# cSLIM-SA_connectors.net
KiCad netlist of a schematic drawn in Altium Designer
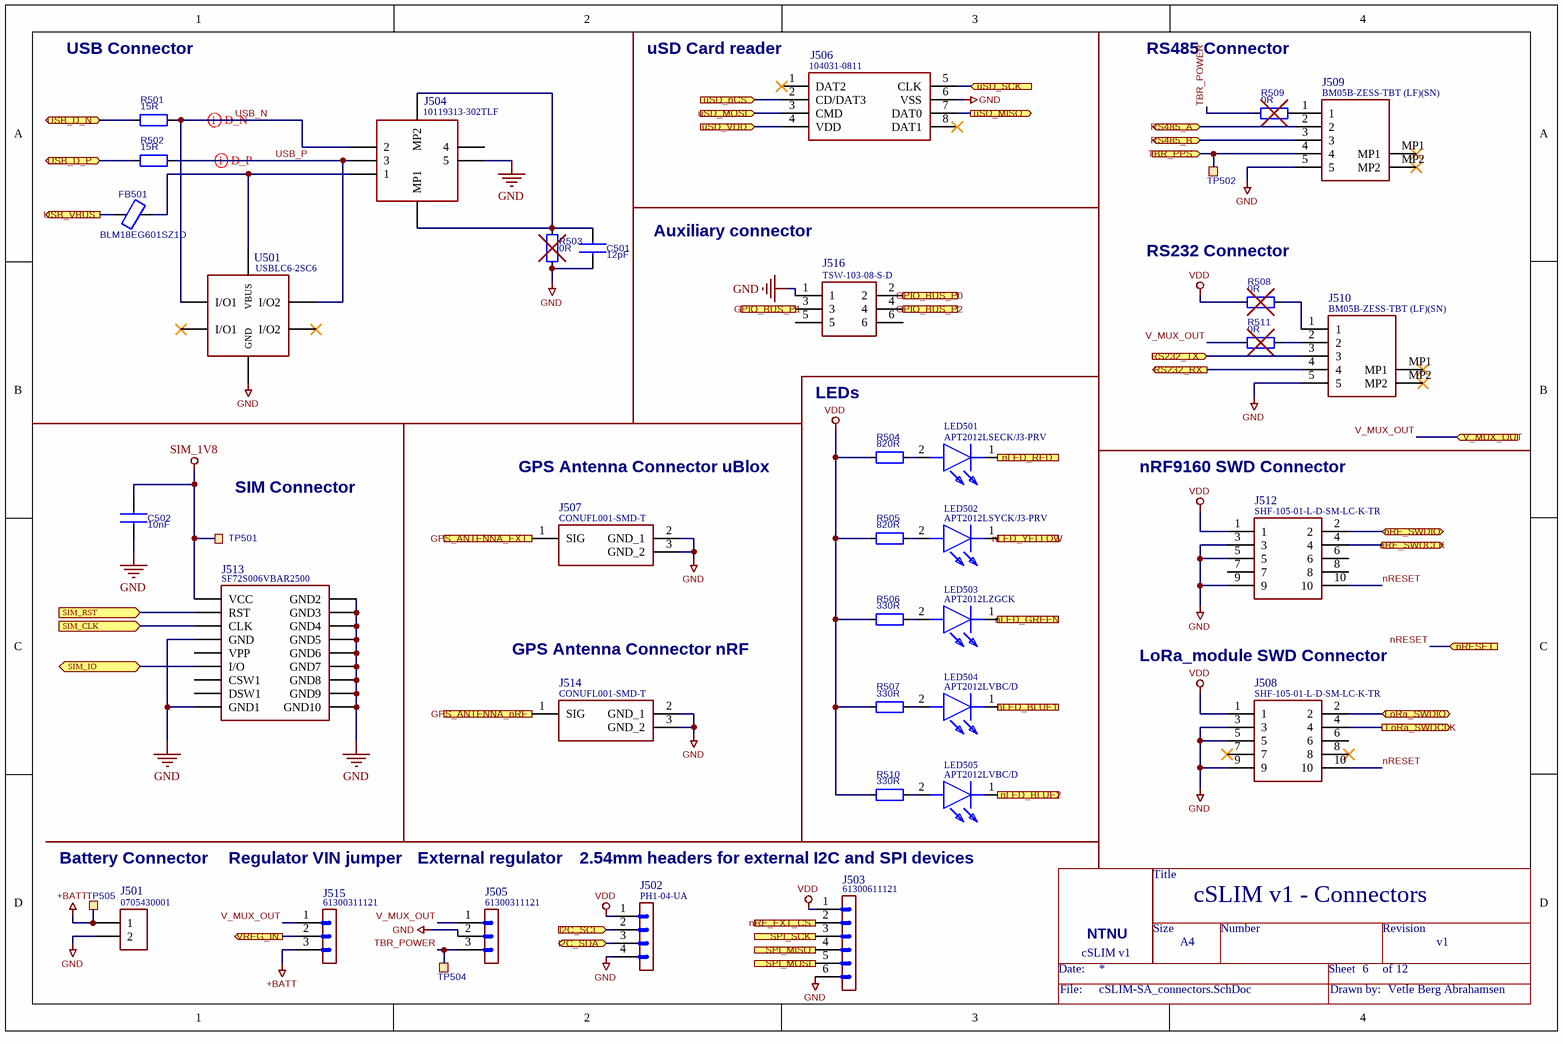
[diagram p0: cSLIM-SA_connectors.SchDoc]

(export (version "E")
  (design (tool "Eeschema 10.0.6"))
  (components
    (comp (ref "C501")
      (value "12pF")
      (footprint "cSLIM-SA:CAPC1608X90N")
      (description "Capacitor")
      (fields (field (name "MANUFACTURER_PART_NUMBER") "0603N120J500CT"))
      (libsource (lib "cSLIM-SA") (part "C"))
    )
    (comp (ref "C502")
      (value "10nF")
      (footprint "cSLIM-SA:CAPC1608X90N")
      (description "Capacitor")
      (fields (field (name "MANUFACTURER_PART_NUMBER") "CL10B103KB8NNNC"))
      (libsource (lib "cSLIM-SA") (part "C"))
    )
    (comp (ref "FB501")
      (value "BLM18EG601SZ1D")
      (footprint "CAPC1608X90N")
      (description "Ferrite bead")
      (libsource (lib "cSLIM-SA") (part "Ferrite_Bead"))
    )
    (comp (ref "J501")
      (value "0705430001")
      (footprint "cSLIM-SA:SHDR2W64P0X254_1X2_737X660X1181P")
      (description "BAT CONN HEADER VERT 2POS 2.54MM")
      (fields
        (field (name "MANUFACTURER_PART_NUMBER") "70543-0001")
        (field (name "MOUSER PART NUMBER") "538-70543-0001")
      )
      (libsource (lib "cSLIM-SA") (part "70543-0001"))
    )
    (comp (ref "J502")
      (value "PH1-04-UA")
      (footprint "cSLIM-SA:HDRV4W64P0X254_1X4_1016X250X901P")
      (description "CONN HEADER VERT 4POS 2.54MM")
      (libsource (lib "cSLIM-SA") (part "PH1-04-UA"))
    )
    (comp (ref "J503")
      (value "61300611121")
      (footprint "cSLIM-SA:HDRV6W64P0X254_1X6_1524X254X869P")
      (description "CONN HEADER VERT 6POS 2.54MM")
      (fields (field (name "MOUSER PART NUMBER") "710-61300611121"))
      (libsource (lib "cSLIM-SA") (part "61300611121"))
    )
    (comp (ref "J504")
      (value "10119313-302TLF")
      (footprint "cSLIM-SA:10119313302TLF")
      (description "USB - mini B USB 2.0 Receptacle Connector 5 Position Through Hole")
      (fields (field (name "MOUSER PART NUMBER") "649-10119313-302TLF"))
      (libsource (lib "cSLIM-SA") (part "10119313-302TLF"))
    )
    (comp (ref "J505")
      (value "61300311121")
      (footprint "cSLIM-SA:HDRV3W64P0X254_1X3_762X254X869P")
      (description "CONN HEADER VERT 3POS 2.54MM")
      (fields (field (name "MOUSER PART NUMBER") "710-61300311121"))
      (libsource (lib "cSLIM-SA") (part "61300311121"))
    )
    (comp (ref "J506")
      (value "104031-0811")
      (footprint "cSLIM-SA:1040310811")
      (description "CONN MICRO SD CARD PUSH-PULL R/A")
      (fields (field (name "MOUSER PART NUMBER") "538-104031-0811"))
      (libsource (lib "cSLIM-SA") (part "104031-0811"))
    )
    (comp (ref "J507")
      (value "CONUFL001-SMD-T")
      (footprint "cSLIM-SA:CONUFL001-SMD")
      (description "CONN UMC JACK STR SMD")
      (fields (field (name "MOUSER PART NUMBER") "712-CONUFL001-SMD-T"))
      (libsource (lib "cSLIM-SA") (part "CONUFL001-SMD-T"))
    )
    (comp (ref "J508")
      (value "SHF-105-01-L-D-SM-LC-K-TR")
      (footprint "cSLIM-SA:SHF10501LDSMLCKTR")
      (description "CONN HEADER SMD 10POS 1.27MM")
      (libsource (lib "cSLIM-SA") (part "SHF-105-01-L-D-SM-LC-K-TR"))
    )
    (comp (ref "J509")
      (value "BM05B-ZESS-TBT (LF)(SN)")
      (footprint "cSLIM-SA:BM05BZESSTBTLFSN")
      (description "RS232/RS485  CONN HEADER SMD 5POS 1.5MM")
      (libsource (lib "cSLIM-SA") (part "BM05B-ZESS-TBT__LF__SN_"))
    )
    (comp (ref "J510")
      (value "BM05B-ZESS-TBT (LF)(SN)")
      (footprint "cSLIM-SA:BM05BZESSTBTLFSN")
      (description "RS232/RS485  CONN HEADER SMD 5POS 1.5MM")
      (libsource (lib "cSLIM-SA") (part "BM05B-ZESS-TBT__LF__SN_"))
    )
    (comp (ref "J512")
      (value "SHF-105-01-L-D-SM-LC-K-TR")
      (footprint "cSLIM-SA:SHF10501LDSMLCKTR")
      (description "CONN HEADER SMD 10POS 1.27MM")
      (libsource (lib "cSLIM-SA") (part "SHF-105-01-L-D-SM-LC-K-TR"))
    )
    (comp (ref "J513")
      (value "SF72S006VBAR2500")
      (footprint "cSLIM-SA:SF72S006VBAR2500")
      (description "NANO SIM CARD PUSH-PUSH")
      (fields (field (name "MOUSER PART NUMBER") "656-SF72S006VBAR2500"))
      (libsource (lib "cSLIM-SA") (part "SF72S006VBAR2500"))
    )
    (comp (ref "J514")
      (value "CONUFL001-SMD-T")
      (footprint "cSLIM-SA:CONUFL001-SMD")
      (description "CONN UMC JACK STR SMD")
      (fields (field (name "MOUSER PART NUMBER") "712-CONUFL001-SMD-T"))
      (libsource (lib "cSLIM-SA") (part "CONUFL001-SMD-T"))
    )
    (comp (ref "J515")
      (value "61300311121")
      (footprint "cSLIM-SA:HDRV3W64P0X254_1X3_762X254X869P")
      (description "CONN HEADER VERT 3POS 2.54MM")
      (fields (field (name "MOUSER PART NUMBER") "710-61300311121"))
      (libsource (lib "cSLIM-SA") (part "61300311121"))
    )
    (comp (ref "J516")
      (value "TSW-103-08-S-D")
      (footprint "cSLIM-SA:HDRV6W64P254_2X3_762X495X838P")
      (description "Auxillary 2x3 conn")
      (fields (field (name "MOUSER PART NUMBER") "200-TSW10308SD"))
      (libsource (lib "cSLIM-SA") (part "TSW-103-08-S-D"))
    )
    (comp (ref "LED501")
      (value "APT2012LSECK/J3-PRV")
      (footprint "cSLIM-SA:LEDC2012X75N")
      (description "LED RED CLEAR 2SMD")
      (fields (field (name "MOUSER PART NUMBER") "604-APT2012LSECKJ3RV"))
      (libsource (lib "cSLIM-SA") (part "APT2012LSECK_J3-PRV"))
    )
    (comp (ref "LED502")
      (value "APT2012LSYCK/J3-PRV")
      (footprint "cSLIM-SA:LEDC2012X85N")
      (description "LED YELLOW CLEAR 2SMD")
      (fields (field (name "MOUSER PART NUMBER") "604-APT2012LSYCKJ3RV"))
      (libsource (lib "cSLIM-SA") (part "APT2012LSYCK_J3-PRV"))
    )
    (comp (ref "LED503")
      (value "APT2012LZGCK")
      (footprint "cSLIM-SA:LEDC2012X85N")
      (description "LED GREEN CLEAR 2SMD")
      (fields (field (name "MOUSER PART NUMBER") "604-APT2012LZGCK"))
      (libsource (lib "cSLIM-SA") (part "APT2012LZGCK"))
    )
    (comp (ref "LED504")
      (value "APT2012LVBC/D")
      (footprint "cSLIM-SA:LEDC2012X85N")
      (description "LED BLUE CLEAR 2SMD")
      (fields (field (name "MOUSER PART NUMBER") "604-APT2012LVBCD"))
      (libsource (lib "cSLIM-SA") (part "APT2012LVBC_D"))
    )
    (comp (ref "LED505")
      (value "APT2012LVBC/D")
      (footprint "cSLIM-SA:LEDC2012X85N")
      (description "LED BLUE CLEAR 2SMD")
      (fields (field (name "MOUSER PART NUMBER") "604-APT2012LVBCD"))
      (libsource (lib "cSLIM-SA") (part "APT2012LVBC_D"))
    )
    (comp (ref "R501")
      (value "15R")
      (footprint "cSLIM-SA:RESC1608X55N")
      (fields (field (name "MANUFACTURER_PART_NUMBER") "RC0603JR-0715RL"))
      (libsource (lib "cSLIM-SA") (part "R"))
    )
    (comp (ref "R502")
      (value "15R")
      (footprint "cSLIM-SA:RESC1608X55N")
      (fields (field (name "MANUFACTURER_PART_NUMBER") "RC0603JR-0715RL"))
      (libsource (lib "cSLIM-SA") (part "R"))
    )
    (comp (ref "R503")
      (value "0R")
      (footprint "cSLIM-SA:RESC1608X55N")
      (fields (field (name "MANUFACTURER_PART_NUMBER") "YJP1608-R001"))
      (libsource (lib "") (part "R_1"))
    )
    (comp (ref "R504")
      (value "820R")
      (footprint "cSLIM-SA:RESC1608X55N")
      (fields (field (name "MANUFACTURER_PART_NUMBER") "RC0603FR-07820RL"))
      (libsource (lib "cSLIM-SA") (part "R"))
    )
    (comp (ref "R505")
      (value "820R")
      (footprint "cSLIM-SA:RESC1608X55N")
      (fields (field (name "MANUFACTURER_PART_NUMBER") "RC0603FR-07820RL"))
      (libsource (lib "cSLIM-SA") (part "R"))
    )
    (comp (ref "R506")
      (value "330R")
      (footprint "cSLIM-SA:RESC1608X55N")
      (fields (field (name "MANUFACTURER_PART_NUMBER") "RC0603FR-07330RL"))
      (libsource (lib "cSLIM-SA") (part "R"))
    )
    (comp (ref "R507")
      (value "330R")
      (footprint "cSLIM-SA:RESC1608X55N")
      (fields (field (name "MANUFACTURER_PART_NUMBER") "RC0603FR-07330RL"))
      (libsource (lib "cSLIM-SA") (part "R"))
    )
    (comp (ref "R508")
      (value "0R")
      (footprint "cSLIM-SA:RESC1608X55N")
      (fields (field (name "MANUFACTURER_PART_NUMBER") "YJP1608-R001"))
      (libsource (lib "cSLIM-SA") (part "R"))
    )
    (comp (ref "R509")
      (value "0R")
      (footprint "cSLIM-SA:RESC1608X55N")
      (fields (field (name "MANUFACTURER_PART_NUMBER") "YJP1608-R001"))
      (libsource (lib "cSLIM-SA") (part "R"))
    )
    (comp (ref "R510")
      (value "330R")
      (footprint "cSLIM-SA:RESC1608X55N")
      (fields (field (name "MANUFACTURER_PART_NUMBER") "RC0603FR-07330RL"))
      (libsource (lib "cSLIM-SA") (part "R"))
    )
    (comp (ref "R511")
      (value "0R")
      (footprint "cSLIM-SA:RESC1608X55N")
      (fields (field (name "MANUFACTURER_PART_NUMBER") "YJP1608-R001"))
      (libsource (lib "cSLIM-SA") (part "R"))
    )
    (comp (ref "TP501")
      (value "TP")
      (footprint "cSLIM-SA:TP_SMD_Ø1.0mm")
      (description "Test points")
      (libsource (lib "") (part "TP_2"))
    )
    (comp (ref "TP502")
      (value "TP")
      (footprint "cSLIM-SA:TP_SMD_Ø1.0mm")
      (description "Test points")
      (libsource (lib "") (part "TP_1"))
    )
    (comp (ref "TP504")
      (value "TP")
      (footprint "cSLIM-SA:TP_SMD_Ø1.0mm")
      (description "Test points")
      (libsource (lib "") (part "TP_1"))
    )
    (comp (ref "TP505")
      (value "TP")
      (footprint "cSLIM-SA:TP_SMD_Ø1.0mm")
      (description "Test points")
      (libsource (lib "cSLIM-SA") (part "TP"))
    )
    (comp (ref "U501")
      (value "USBLC6-2SC6")
      (footprint "cSLIM-SA:SOT95P280X145-6N")
      (description "17V Clamp 5A (8/20µs) Ipp Tvs Diode Surface Mount SOT-23-6")
      (fields (field (name "MOUSER PART NUMBER") "511-USBLC6-2SC6"))
      (libsource (lib "cSLIM-SA") (part "USBLC6-2SC6"))
    )
  )
  (nets
    (net (code "1") (name "+BATT") (class "Default")
      (node (ref "J501") (pin "1") (pinfunction "1_1") (pintype "passive"))
      (node (ref "J515") (pin "3") (pinfunction "3_3") (pintype "passive"))
      (node (ref "TP505") (pin "1") (pinfunction "1_1") (pintype "passive"))
    )
    (net (code "2") (name "/GPIO_BUS_P0") (class "Default")
      (node (ref "J516") (pin "2") (pinfunction "2_2") (pintype "passive"))
    )
    (net (code "3") (name "/GPIO_BUS_P1") (class "Default")
      (node (ref "J516") (pin "3") (pinfunction "3_3") (pintype "passive"))
    )
    (net (code "4") (name "/GPIO_BUS_P2") (class "Default")
      (node (ref "J516") (pin "4") (pinfunction "4_4") (pintype "passive"))
    )
    (net (code "5") (name "/GPS_ANTENNA_EXT") (class "Default")
      (node (ref "J507") (pin "1") (pinfunction "SIG_1") (pintype "passive"))
    )
    (net (code "6") (name "/GPS_ANTENNA_nRF") (class "Default")
      (node (ref "J514") (pin "1") (pinfunction "SIG_1") (pintype "passive"))
    )
    (net (code "7") (name "/I2C_SCL") (class "Default")
      (node (ref "J502") (pin "2") (pinfunction "2_2") (pintype "passive"))
    )
    (net (code "8") (name "/I2C_SDA") (class "Default")
      (node (ref "J502") (pin "3") (pinfunction "3_3") (pintype "passive"))
    )
    (net (code "9") (name "/LoRa_SWDCLK") (class "Default")
      (node (ref "J508") (pin "4") (pinfunction "4_4") (pintype "passive"))
    )
    (net (code "10") (name "/LoRa_SWDIO") (class "Default")
      (node (ref "J508") (pin "2") (pinfunction "2_2") (pintype "passive"))
    )
    (net (code "11") (name "/RS232_RX") (class "Default")
      (node (ref "J510") (pin "4") (pinfunction "4_4") (pintype "passive"))
    )
    (net (code "12") (name "/RS232_TX") (class "Default")
      (node (ref "J510") (pin "3") (pinfunction "3_3") (pintype "passive"))
    )
    (net (code "13") (name "/RS485_A") (class "Default")
      (node (ref "J509") (pin "2") (pinfunction "2_2") (pintype "passive"))
    )
    (net (code "14") (name "/RS485_B") (class "Default")
      (node (ref "J509") (pin "3") (pinfunction "3_3") (pintype "passive"))
    )
    (net (code "15") (name "/SIM_CLK") (class "Default")
      (node (ref "J513") (pin "C3") (pinfunction "CLK_C3") (pintype "passive"))
    )
    (net (code "16") (name "/SIM_IO") (class "Default")
      (node (ref "J513") (pin "C7") (pinfunction "I/O_C7") (pintype "passive"))
    )
    (net (code "17") (name "/SIM_RST") (class "Default")
      (node (ref "J513") (pin "C2") (pinfunction "RST_C2") (pintype "passive"))
    )
    (net (code "18") (name "/SPI_MISO") (class "Default")
      (node (ref "J503") (pin "4") (pinfunction "4_4") (pintype "passive"))
    )
    (net (code "19") (name "/SPI_MOSI") (class "Default")
      (node (ref "J503") (pin "5") (pinfunction "5_5") (pintype "passive"))
    )
    (net (code "20") (name "/SPI_SCK") (class "Default")
      (node (ref "J503") (pin "3") (pinfunction "3_3") (pintype "passive"))
    )
    (net (code "21") (name "/TBR_POWER") (class "Default")
      (node (ref "J505") (pin "3") (pinfunction "3_3") (pintype "passive"))
      (node (ref "R509") (pin "2") (pinfunction "2_2") (pintype "passive"))
      (node (ref "TP504") (pin "1") (pinfunction "1_1") (pintype "passive"))
    )
    (net (code "22") (name "/TBR_PPS") (class "Default")
      (node (ref "J509") (pin "4") (pinfunction "4_4") (pintype "passive"))
      (node (ref "TP502") (pin "1") (pinfunction "1_1") (pintype "passive"))
    )
    (net (code "23") (name "/USB_D_N") (class "Default")
      (node (ref "R501") (pin "2") (pinfunction "2_2") (pintype "passive"))
    )
    (net (code "24") (name "/USB_D_P") (class "Default")
      (node (ref "R502") (pin "2") (pinfunction "2_2") (pintype "passive"))
    )
    (net (code "25") (name "/USB_N") (class "Default")
      (node (ref "J504") (pin "2") (pinfunction "2_2") (pintype "passive"))
      (node (ref "R501") (pin "1") (pinfunction "1_1") (pintype "passive"))
      (node (ref "U501") (pin "6") (pinfunction "I/O1_6") (pintype "passive"))
    )
    (net (code "26") (name "/USB_P") (class "Default")
      (node (ref "J504") (pin "3") (pinfunction "3_3") (pintype "passive"))
      (node (ref "R502") (pin "1") (pinfunction "1_1") (pintype "passive"))
      (node (ref "U501") (pin "4") (pinfunction "I/O2_4") (pintype "passive"))
    )
    (net (code "27") (name "/USB_VBUS") (class "Default")
      (node (ref "FB501") (pin "1") (pinfunction "1_1") (pintype "passive"))
    )
    (net (code "28") (name "/VREG_IN") (class "Default")
      (node (ref "J515") (pin "2") (pinfunction "2_2") (pintype "passive"))
    )
    (net (code "29") (name "/V_MUX_OUT") (class "Default")
      (node (ref "J505") (pin "1") (pinfunction "1_1") (pintype "passive"))
      (node (ref "J515") (pin "1") (pinfunction "1_1") (pintype "passive"))
      (node (ref "R511") (pin "2") (pinfunction "2_2") (pintype "passive"))
    )
    (net (code "30") (name "/nLED_BLUE1") (class "Default")
      (node (ref "LED504") (pin "1") (pinfunction "K_1") (pintype "passive"))
    )
    (net (code "31") (name "/nLED_BLUE2") (class "Default")
      (node (ref "LED505") (pin "1") (pinfunction "K_1") (pintype "passive"))
    )
    (net (code "32") (name "/nLED_GREEN") (class "Default")
      (node (ref "LED503") (pin "1") (pinfunction "K_1") (pintype "passive"))
    )
    (net (code "33") (name "/nLED_RED") (class "Default")
      (node (ref "LED501") (pin "1") (pinfunction "K_1") (pintype "passive"))
    )
    (net (code "34") (name "/nLED_YELLOW") (class "Default")
      (node (ref "LED502") (pin "1") (pinfunction "K_1") (pintype "passive"))
    )
    (net (code "35") (name "/nRESET") (class "Default")
      (node (ref "J508") (pin "10") (pinfunction "10_10") (pintype "passive"))
      (node (ref "J512") (pin "10") (pinfunction "10_10") (pintype "passive"))
    )
    (net (code "36") (name "/nRF_EXT_CS") (class "Default")
      (node (ref "J503") (pin "2") (pinfunction "2_2") (pintype "passive"))
    )
    (net (code "37") (name "/nRF_SWDCLK") (class "Default")
      (node (ref "J512") (pin "4") (pinfunction "4_4") (pintype "passive"))
    )
    (net (code "38") (name "/nRF_SWDIO") (class "Default")
      (node (ref "J512") (pin "2") (pinfunction "2_2") (pintype "passive"))
    )
    (net (code "39") (name "/uSD_MISO") (class "Default")
      (node (ref "J506") (pin "7") (pinfunction "DAT0_7") (pintype "passive"))
    )
    (net (code "40") (name "/uSD_MOSI") (class "Default")
      (node (ref "J506") (pin "3") (pinfunction "CMD_3") (pintype "passive"))
    )
    (net (code "41") (name "/uSD_SCK") (class "Default")
      (node (ref "J506") (pin "5") (pinfunction "CLK_5") (pintype "passive"))
    )
    (net (code "42") (name "/uSD_VDD") (class "Default")
      (node (ref "J506") (pin "4") (pinfunction "VDD_4") (pintype "passive"))
    )
    (net (code "43") (name "/uSD_nCS") (class "Default")
      (node (ref "J506") (pin "2") (pinfunction "CD/DAT3_2") (pintype "passive"))
    )
    (net (code "44") (name "GND") (class "Default")
      (node (ref "C501") (pin "2") (pinfunction "2_2") (pintype "passive"))
      (node (ref "C502") (pin "2") (pinfunction "2_2") (pintype "passive"))
      (node (ref "J501") (pin "2") (pinfunction "2_2") (pintype "passive"))
      (node (ref "J502") (pin "4") (pinfunction "4_4") (pintype "passive"))
      (node (ref "J503") (pin "6") (pinfunction "6_6") (pintype "passive"))
      (node (ref "J504") (pin "5") (pinfunction "5_5") (pintype "passive"))
      (node (ref "J505") (pin "2") (pinfunction "2_2") (pintype "passive"))
      (node (ref "J506") (pin "6") (pinfunction "VSS_6") (pintype "passive"))
      (node (ref "J507") (pin "2") (pinfunction "GND_1_2") (pintype "passive"))
      (node (ref "J507") (pin "3") (pinfunction "GND_2_3") (pintype "passive"))
      (node (ref "J508") (pin "3") (pinfunction "3_3") (pintype "passive"))
      (node (ref "J508") (pin "5") (pinfunction "5_5") (pintype "passive"))
      (node (ref "J508") (pin "9") (pinfunction "9_9") (pintype "passive"))
      (node (ref "J509") (pin "5") (pinfunction "5_5") (pintype "passive"))
      (node (ref "J510") (pin "5") (pinfunction "5_5") (pintype "passive"))
      (node (ref "J512") (pin "3") (pinfunction "3_3") (pintype "passive"))
      (node (ref "J512") (pin "5") (pinfunction "5_5") (pintype "passive"))
      (node (ref "J512") (pin "9") (pinfunction "9_9") (pintype "passive"))
      (node (ref "J513") (pin "C5") (pinfunction "GND_C5") (pintype "passive"))
      (node (ref "J513") (pin "GND1") (pinfunction "GND1_GND1") (pintype "passive"))
      (node (ref "J513") (pin "GND10") (pinfunction "GND10_GND10") (pintype "passive"))
      (node (ref "J513") (pin "GND2") (pinfunction "GND2_GND2") (pintype "passive"))
      (node (ref "J513") (pin "GND3") (pinfunction "GND3_GND3") (pintype "passive"))
      (node (ref "J513") (pin "GND4") (pinfunction "GND4_GND4") (pintype "passive"))
      (node (ref "J513") (pin "GND5") (pinfunction "GND5_GND5") (pintype "passive"))
      (node (ref "J513") (pin "GND6") (pinfunction "GND6_GND6") (pintype "passive"))
      (node (ref "J513") (pin "GND7") (pinfunction "GND7_GND7") (pintype "passive"))
      (node (ref "J513") (pin "GND8") (pinfunction "GND8_GND8") (pintype "passive"))
      (node (ref "J513") (pin "GND9") (pinfunction "GND9_GND9") (pintype "passive"))
      (node (ref "J514") (pin "2") (pinfunction "GND_1_2") (pintype "passive"))
      (node (ref "J514") (pin "3") (pinfunction "GND_2_3") (pintype "passive"))
      (node (ref "J516") (pin "1") (pinfunction "1_1") (pintype "passive"))
      (node (ref "R503") (pin "2") (pinfunction "2_2") (pintype "passive"))
      (node (ref "U501") (pin "2") (pinfunction "GND_2") (pintype "passive"))
    )
    (net (code "45") (name "Net-(C501-Pad1)") (class "Default")
      (node (ref "C501") (pin "1") (pinfunction "1_1") (pintype "passive"))
      (node (ref "J504") (pin "MP1") (pinfunction "MP1_MP1") (pintype "passive"))
      (node (ref "J504") (pin "MP2") (pinfunction "MP2_MP2") (pintype "passive"))
      (node (ref "R503") (pin "1") (pinfunction "1_1") (pintype "passive"))
    )
    (net (code "46") (name "Net-(J509-Pad1)") (class "Default")
      (node (ref "J509") (pin "1") (pinfunction "1_1") (pintype "passive"))
      (node (ref "R509") (pin "1") (pinfunction "1_1") (pintype "passive"))
    )
    (net (code "47") (name "Net-(J510-Pad1)") (class "Default")
      (node (ref "J510") (pin "1") (pinfunction "1_1") (pintype "passive"))
      (node (ref "R508") (pin "1") (pinfunction "1_1") (pintype "passive"))
    )
    (net (code "48") (name "Net-(J510-Pad2)") (class "Default")
      (node (ref "J510") (pin "2") (pinfunction "2_2") (pintype "passive"))
      (node (ref "R511") (pin "1") (pinfunction "1_1") (pintype "passive"))
    )
    (net (code "49") (name "Net-(LED501-A)") (class "Default")
      (node (ref "LED501") (pin "2") (pinfunction "A_2") (pintype "passive"))
      (node (ref "R504") (pin "1") (pinfunction "1_1") (pintype "passive"))
    )
    (net (code "50") (name "Net-(LED502-A)") (class "Default")
      (node (ref "LED502") (pin "2") (pinfunction "A_2") (pintype "passive"))
      (node (ref "R505") (pin "1") (pinfunction "1_1") (pintype "passive"))
    )
    (net (code "51") (name "Net-(LED503-A)") (class "Default")
      (node (ref "LED503") (pin "2") (pinfunction "A_2") (pintype "passive"))
      (node (ref "R506") (pin "1") (pinfunction "1_1") (pintype "passive"))
    )
    (net (code "52") (name "Net-(LED504-A)") (class "Default")
      (node (ref "LED504") (pin "2") (pinfunction "A_2") (pintype "passive"))
      (node (ref "R507") (pin "1") (pinfunction "1_1") (pintype "passive"))
    )
    (net (code "53") (name "Net-(LED505-A)") (class "Default")
      (node (ref "LED505") (pin "2") (pinfunction "A_2") (pintype "passive"))
      (node (ref "R510") (pin "1") (pinfunction "1_1") (pintype "passive"))
    )
    (net (code "54") (name "Net-(U501-VBUS)") (class "Default")
      (node (ref "FB501") (pin "2") (pinfunction "2_2") (pintype "passive"))
      (node (ref "J504") (pin "1") (pinfunction "1_1") (pintype "passive"))
      (node (ref "U501") (pin "5") (pinfunction "VBUS_5") (pintype "passive"))
    )
    (net (code "55") (name "SIM_1V8") (class "Default")
      (node (ref "C502") (pin "1") (pinfunction "1_1") (pintype "passive"))
      (node (ref "J513") (pin "C1") (pinfunction "VCC_C1") (pintype "passive"))
      (node (ref "TP501") (pin "1") (pinfunction "1_1") (pintype "passive"))
    )
    (net (code "56") (name "VDD") (class "Default")
      (node (ref "J502") (pin "1") (pinfunction "1_1") (pintype "passive"))
      (node (ref "J503") (pin "1") (pinfunction "1_1") (pintype "passive"))
      (node (ref "J508") (pin "1") (pinfunction "1_1") (pintype "passive"))
      (node (ref "J512") (pin "1") (pinfunction "1_1") (pintype "passive"))
      (node (ref "R504") (pin "2") (pinfunction "2_2") (pintype "passive"))
      (node (ref "R505") (pin "2") (pinfunction "2_2") (pintype "passive"))
      (node (ref "R506") (pin "2") (pinfunction "2_2") (pintype "passive"))
      (node (ref "R507") (pin "2") (pinfunction "2_2") (pintype "passive"))
      (node (ref "R508") (pin "2") (pinfunction "2_2") (pintype "passive"))
      (node (ref "R510") (pin "2") (pinfunction "2_2") (pintype "passive"))
    )
    (net (code "57") (name "unconnected-(J504-Pad4)") (class "Default")
      (node (ref "J504") (pin "4") (pinfunction "4_4") (pintype "passive"))
    )
    (net (code "58") (name "unconnected-(J506-DAT1-Pad8)") (class "Default")
      (node (ref "J506") (pin "8") (pinfunction "DAT1_8") (pintype "passive+no_connect"))
    )
    (net (code "59") (name "unconnected-(J506-DAT2-Pad1)") (class "Default")
      (node (ref "J506") (pin "1") (pinfunction "DAT2_1") (pintype "passive+no_connect"))
    )
    (net (code "60") (name "unconnected-(J508-Pad6)") (class "Default")
      (node (ref "J508") (pin "6") (pinfunction "6_6") (pintype "passive"))
    )
    (net (code "61") (name "unconnected-(J508-Pad7)") (class "Default")
      (node (ref "J508") (pin "7") (pinfunction "7_7") (pintype "passive+no_connect"))
    )
    (net (code "62") (name "unconnected-(J508-Pad8)") (class "Default")
      (node (ref "J508") (pin "8") (pinfunction "8_8") (pintype "passive+no_connect"))
    )
    (net (code "63") (name "unconnected-(J509-PadMP1)") (class "Default")
      (node (ref "J509") (pin "MP1") (pinfunction "MP1_MP1") (pintype "passive+no_connect"))
    )
    (net (code "64") (name "unconnected-(J509-PadMP2)") (class "Default")
      (node (ref "J509") (pin "MP2") (pinfunction "MP2_MP2") (pintype "passive+no_connect"))
    )
    (net (code "65") (name "unconnected-(J510-PadMP1)") (class "Default")
      (node (ref "J510") (pin "MP1") (pinfunction "MP1_MP1") (pintype "passive+no_connect"))
    )
    (net (code "66") (name "unconnected-(J510-PadMP2)") (class "Default")
      (node (ref "J510") (pin "MP2") (pinfunction "MP2_MP2") (pintype "passive+no_connect"))
    )
    (net (code "67") (name "unconnected-(J512-Pad6)") (class "Default")
      (node (ref "J512") (pin "6") (pinfunction "6_6") (pintype "passive"))
    )
    (net (code "68") (name "unconnected-(J512-Pad7)") (class "Default")
      (node (ref "J512") (pin "7") (pinfunction "7_7") (pintype "passive"))
    )
    (net (code "69") (name "unconnected-(J512-Pad8)") (class "Default")
      (node (ref "J512") (pin "8") (pinfunction "8_8") (pintype "passive"))
    )
    (net (code "70") (name "unconnected-(J513-PadCSW1)") (class "Default")
      (node (ref "J513") (pin "CSW1") (pinfunction "CSW1_CSW1") (pintype "passive"))
    )
    (net (code "71") (name "unconnected-(J513-PadDSW1)") (class "Default")
      (node (ref "J513") (pin "DSW1") (pinfunction "DSW1_DSW1") (pintype "passive"))
    )
    (net (code "72") (name "unconnected-(J513-VPP-PadC6)") (class "Default")
      (node (ref "J513") (pin "C6") (pinfunction "VPP_C6") (pintype "passive"))
    )
    (net (code "73") (name "unconnected-(J516-Pad5)") (class "Default")
      (node (ref "J516") (pin "5") (pinfunction "5_5") (pintype "passive"))
    )
    (net (code "74") (name "unconnected-(J516-Pad6)") (class "Default")
      (node (ref "J516") (pin "6") (pinfunction "6_6") (pintype "passive"))
    )
    (net (code "75") (name "unconnected-(U501-I{slash}O1-Pad1)") (class "Default")
      (node (ref "U501") (pin "1") (pinfunction "I/O1_1") (pintype "passive+no_connect"))
    )
    (net (code "76") (name "unconnected-(U501-I{slash}O2-Pad3)") (class "Default")
      (node (ref "U501") (pin "3") (pinfunction "I/O2_3") (pintype "passive+no_connect"))
    )
  )
)
